# Ionic_Skin_Sensorized_Glove.net
KiCad netlist of a schematic drawn in EAGLE
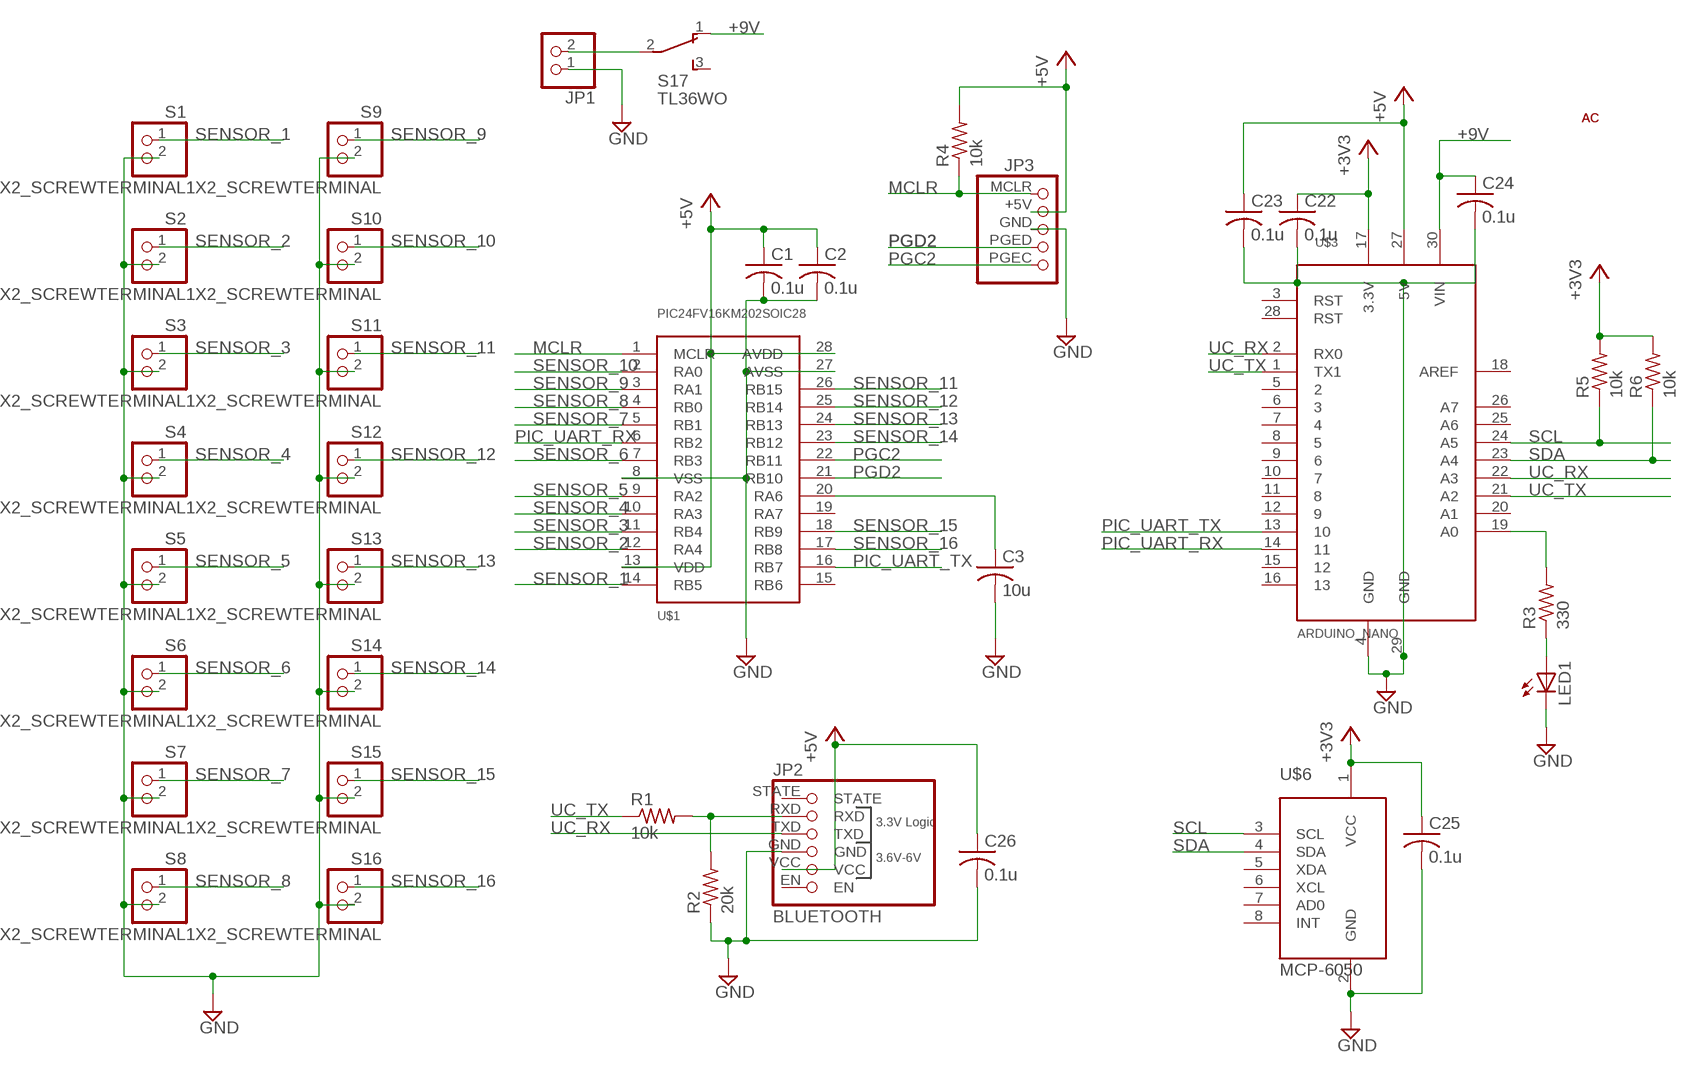
[diagram p0: schematic, sheet 1]

(export (version "E")
  (design (tool "Eeschema 10.0.6"))
  (components
    (comp (ref "C1")
      (value "0.1u")
      (footprint "eagle-import:C0805")
      (libsource (lib "eagle-import") (part "C-USC0805"))
    )
    (comp (ref "C2")
      (value "0.1u")
      (footprint "eagle-import:C0805")
      (libsource (lib "eagle-import") (part "C-USC0805"))
    )
    (comp (ref "C3")
      (value "10u")
      (footprint "eagle-import:C0805")
      (libsource (lib "eagle-import") (part "C-USC0805"))
    )
    (comp (ref "C22")
      (value "0.1u")
      (footprint "eagle-import:C0805")
      (libsource (lib "eagle-import") (part "C-USC0805"))
    )
    (comp (ref "C23")
      (value "0.1u")
      (footprint "eagle-import:C0805")
      (libsource (lib "eagle-import") (part "C-USC0805"))
    )
    (comp (ref "C24")
      (value "0.1u")
      (footprint "eagle-import:C0805")
      (libsource (lib "eagle-import") (part "C-USC0805"))
    )
    (comp (ref "C25")
      (value "0.1u")
      (footprint "eagle-import:C0805")
      (libsource (lib "eagle-import") (part "C-USC0805"))
    )
    (comp (ref "C26")
      (value "0.1u")
      (footprint "eagle-import:C0805")
      (libsource (lib "eagle-import") (part "C-USC0805"))
    )
    (comp (ref "JP1")
      (value "PINHD-1X2")
      (footprint "eagle-import:1X02")
      (libsource (lib "eagle-import") (part "PINHD-1X2"))
    )
    (comp (ref "JP2")
      (value "BLUETOOTH")
      (footprint "eagle-import:HC-06")
      (libsource (lib "eagle-import") (part "HC-06"))
    )
    (comp (ref "JP3")
      (value "PICKIT/90")
      (footprint "eagle-import:PICKIT_90")
      (libsource (lib "eagle-import") (part "PICKIT/90"))
    )
    (comp (ref "LED1")
      (value "LEDCHIPLED_0805")
      (footprint "eagle-import:CHIPLED_0805")
      (libsource (lib "eagle-import") (part "LEDCHIPLED_0805"))
    )
    (comp (ref "R1")
      (value "10k")
      (footprint "eagle-import:R0805")
      (libsource (lib "eagle-import") (part "R-US_R0805"))
    )
    (comp (ref "R2")
      (value "20k")
      (footprint "eagle-import:R0805")
      (libsource (lib "eagle-import") (part "R-US_R0805"))
    )
    (comp (ref "R3")
      (value "330")
      (footprint "eagle-import:R0805")
      (libsource (lib "eagle-import") (part "R-US_R0805"))
    )
    (comp (ref "R4")
      (value "10k")
      (footprint "eagle-import:R0805")
      (libsource (lib "eagle-import") (part "R-US_R0805"))
    )
    (comp (ref "R5")
      (value "10k")
      (footprint "eagle-import:R0805")
      (libsource (lib "eagle-import") (part "R-US_R0805"))
    )
    (comp (ref "R6")
      (value "10k")
      (footprint "eagle-import:R0805")
      (libsource (lib "eagle-import") (part "R-US_R0805"))
    )
    (comp (ref "S1")
      (value "1X2_SCREWTERMINAL")
      (footprint "eagle-import:1X2-2.54MM")
      (libsource (lib "eagle-import") (part "1X2_SCREWTERMINAL"))
    )
    (comp (ref "S2")
      (value "1X2_SCREWTERMINAL")
      (footprint "eagle-import:1X2-2.54MM")
      (libsource (lib "eagle-import") (part "1X2_SCREWTERMINAL"))
    )
    (comp (ref "S3")
      (value "1X2_SCREWTERMINAL")
      (footprint "eagle-import:1X2-2.54MM")
      (libsource (lib "eagle-import") (part "1X2_SCREWTERMINAL"))
    )
    (comp (ref "S4")
      (value "1X2_SCREWTERMINAL")
      (footprint "eagle-import:1X2-2.54MM")
      (libsource (lib "eagle-import") (part "1X2_SCREWTERMINAL"))
    )
    (comp (ref "S5")
      (value "1X2_SCREWTERMINAL")
      (footprint "eagle-import:1X2-2.54MM")
      (libsource (lib "eagle-import") (part "1X2_SCREWTERMINAL"))
    )
    (comp (ref "S6")
      (value "1X2_SCREWTERMINAL")
      (footprint "eagle-import:1X2-2.54MM")
      (libsource (lib "eagle-import") (part "1X2_SCREWTERMINAL"))
    )
    (comp (ref "S7")
      (value "1X2_SCREWTERMINAL")
      (footprint "eagle-import:1X2-2.54MM")
      (libsource (lib "eagle-import") (part "1X2_SCREWTERMINAL"))
    )
    (comp (ref "S8")
      (value "1X2_SCREWTERMINAL")
      (footprint "eagle-import:1X2-2.54MM")
      (libsource (lib "eagle-import") (part "1X2_SCREWTERMINAL"))
    )
    (comp (ref "S9")
      (value "1X2_SCREWTERMINAL")
      (footprint "eagle-import:1X2-2.54MM")
      (libsource (lib "eagle-import") (part "1X2_SCREWTERMINAL"))
    )
    (comp (ref "S10")
      (value "1X2_SCREWTERMINAL")
      (footprint "eagle-import:1X2-2.54MM")
      (libsource (lib "eagle-import") (part "1X2_SCREWTERMINAL"))
    )
    (comp (ref "S11")
      (value "1X2_SCREWTERMINAL")
      (footprint "eagle-import:1X2-2.54MM")
      (libsource (lib "eagle-import") (part "1X2_SCREWTERMINAL"))
    )
    (comp (ref "S12")
      (value "1X2_SCREWTERMINAL")
      (footprint "eagle-import:1X2-2.54MM")
      (libsource (lib "eagle-import") (part "1X2_SCREWTERMINAL"))
    )
    (comp (ref "S13")
      (value "1X2_SCREWTERMINAL")
      (footprint "eagle-import:1X2-2.54MM")
      (libsource (lib "eagle-import") (part "1X2_SCREWTERMINAL"))
    )
    (comp (ref "S14")
      (value "1X2_SCREWTERMINAL")
      (footprint "eagle-import:1X2-2.54MM")
      (libsource (lib "eagle-import") (part "1X2_SCREWTERMINAL"))
    )
    (comp (ref "S15")
      (value "1X2_SCREWTERMINAL")
      (footprint "eagle-import:1X2-2.54MM")
      (libsource (lib "eagle-import") (part "1X2_SCREWTERMINAL"))
    )
    (comp (ref "S16")
      (value "1X2_SCREWTERMINAL")
      (footprint "eagle-import:1X2-2.54MM")
      (libsource (lib "eagle-import") (part "1X2_SCREWTERMINAL"))
    )
    (comp (ref "S17")
      (value "TL36WO")
      (footprint "eagle-import:TL3XWO")
      (libsource (lib "eagle-import") (part "TL36WO"))
    )
    (comp (ref "U$1")
      (value "PIC24FV16KM202SOIC28")
      (footprint "eagle-import:SOIC28")
      (libsource (lib "eagle-import") (part "PIC24FV16KM202SOIC28"))
    )
    (comp (ref "U$3")
      (value "ARDUINO_NANO")
      (footprint "eagle-import:ARDUINO_NANO")
      (libsource (lib "eagle-import") (part "ARDUINO_NANO"))
    )
    (comp (ref "U$6")
      (value "MCP-6050")
      (footprint "eagle-import:MCP-6050_BREAKOUT")
      (libsource (lib "eagle-import") (part "MCP-6050"))
    )
    (comp (ref "U$7")
      (value "AC_TOP")
      (footprint "eagle-import:AC_TOP")
      (libsource (lib "eagle-import") (part "AC_TOP"))
    )
    (comp (ref "U$8")
      (value "AC_BOTTOM")
      (footprint "eagle-import:AC_BOTTOM")
      (libsource (lib "eagle-import") (part "AC_BOTTOM"))
    )
  )
  (nets
    (net (code "1") (name "+3V3") (class "Default")
      (node (ref "C22") (pin "1") (pinfunction "1_1") (pintype "passive"))
      (node (ref "C25") (pin "1") (pinfunction "1_1") (pintype "passive"))
      (node (ref "R5") (pin "2") (pinfunction "2_2") (pintype "passive"))
      (node (ref "R6") (pin "2") (pinfunction "2_2") (pintype "passive"))
      (node (ref "U$3") (pin "17") (pinfunction "3.3V_17") (pintype "bidirectional"))
      (node (ref "U$6") (pin "1") (pinfunction "VCC_1") (pintype "bidirectional"))
    )
    (net (code "2") (name "+5V") (class "Default")
      (node (ref "C1") (pin "1") (pinfunction "1_1") (pintype "passive"))
      (node (ref "C2") (pin "1") (pinfunction "1_1") (pintype "passive"))
      (node (ref "C23") (pin "1") (pinfunction "1_1") (pintype "passive"))
      (node (ref "C26") (pin "1") (pinfunction "1_1") (pintype "passive"))
      (node (ref "JP2") (pin "VCC") (pinfunction "VCC_VCC") (pintype "bidirectional"))
      (node (ref "JP3") (pin "+5V") (pinfunction "2_+5V") (pintype "passive"))
      (node (ref "R4") (pin "2") (pinfunction "2_2") (pintype "passive"))
      (node (ref "U$1") (pin "13") (pinfunction "VDD_13") (pintype "bidirectional"))
      (node (ref "U$1") (pin "28") (pinfunction "AVDD_28") (pintype "bidirectional"))
      (node (ref "U$3") (pin "27") (pinfunction "5V_27") (pintype "bidirectional"))
    )
    (net (code "3") (name "/+9V") (class "Default")
      (node (ref "C24") (pin "1") (pinfunction "1_1") (pintype "passive"))
      (node (ref "S17") (pin "1") (pinfunction "O_1") (pintype "passive"))
      (node (ref "U$3") (pin "30") (pinfunction "VIN_30") (pintype "bidirectional"))
    )
    (net (code "4") (name "/MCLR") (class "Default")
      (node (ref "JP3") (pin "MCLR") (pinfunction "1_MCLR") (pintype "passive"))
      (node (ref "R4") (pin "1") (pinfunction "1_1") (pintype "passive"))
      (node (ref "U$1") (pin "1") (pinfunction "MCLR_1") (pintype "bidirectional"))
    )
    (net (code "5") (name "/PGC2") (class "Default")
      (node (ref "JP3") (pin "PGEC") (pinfunction "5_PGEC") (pintype "passive"))
      (node (ref "U$1") (pin "22") (pinfunction "RB11_22") (pintype "bidirectional"))
    )
    (net (code "6") (name "/PGD2") (class "Default")
      (node (ref "JP3") (pin "PGED") (pinfunction "4_PGED") (pintype "passive"))
      (node (ref "U$1") (pin "21") (pinfunction "RB10_21") (pintype "bidirectional"))
    )
    (net (code "7") (name "/PIC_UART_RX") (class "Default")
      (node (ref "U$1") (pin "6") (pinfunction "RB2_6") (pintype "bidirectional"))
      (node (ref "U$3") (pin "14") (pinfunction "11_14") (pintype "bidirectional"))
    )
    (net (code "8") (name "/PIC_UART_TX") (class "Default")
      (node (ref "U$1") (pin "16") (pinfunction "RB7_16") (pintype "bidirectional"))
      (node (ref "U$3") (pin "13") (pinfunction "10_13") (pintype "bidirectional"))
    )
    (net (code "9") (name "/SCL") (class "Default")
      (node (ref "R5") (pin "1") (pinfunction "1_1") (pintype "passive"))
      (node (ref "U$3") (pin "24") (pinfunction "A5_24") (pintype "bidirectional"))
      (node (ref "U$6") (pin "3") (pinfunction "SCL_3") (pintype "bidirectional"))
    )
    (net (code "10") (name "/SDA") (class "Default")
      (node (ref "R6") (pin "1") (pinfunction "1_1") (pintype "passive"))
      (node (ref "U$3") (pin "23") (pinfunction "A4_23") (pintype "bidirectional"))
      (node (ref "U$6") (pin "4") (pinfunction "SDA_4") (pintype "bidirectional"))
    )
    (net (code "11") (name "/SENSOR_1") (class "Default")
      (node (ref "S1") (pin "1") (pinfunction "1_1") (pintype "passive"))
      (node (ref "U$1") (pin "14") (pinfunction "RB5_14") (pintype "bidirectional"))
    )
    (net (code "12") (name "/SENSOR_2") (class "Default")
      (node (ref "S2") (pin "1") (pinfunction "1_1") (pintype "passive"))
      (node (ref "U$1") (pin "12") (pinfunction "RA4_12") (pintype "bidirectional"))
    )
    (net (code "13") (name "/SENSOR_3") (class "Default")
      (node (ref "S3") (pin "1") (pinfunction "1_1") (pintype "passive"))
      (node (ref "U$1") (pin "11") (pinfunction "RB4_11") (pintype "bidirectional"))
    )
    (net (code "14") (name "/SENSOR_4") (class "Default")
      (node (ref "S4") (pin "1") (pinfunction "1_1") (pintype "passive"))
      (node (ref "U$1") (pin "10") (pinfunction "RA3_10") (pintype "bidirectional"))
    )
    (net (code "15") (name "/SENSOR_5") (class "Default")
      (node (ref "S5") (pin "1") (pinfunction "1_1") (pintype "passive"))
      (node (ref "U$1") (pin "9") (pinfunction "RA2_9") (pintype "bidirectional"))
    )
    (net (code "16") (name "/SENSOR_6") (class "Default")
      (node (ref "S6") (pin "1") (pinfunction "1_1") (pintype "passive"))
      (node (ref "U$1") (pin "7") (pinfunction "RB3_7") (pintype "bidirectional"))
    )
    (net (code "17") (name "/SENSOR_7") (class "Default")
      (node (ref "S7") (pin "1") (pinfunction "1_1") (pintype "passive"))
      (node (ref "U$1") (pin "5") (pinfunction "RB1_5") (pintype "bidirectional"))
    )
    (net (code "18") (name "/SENSOR_8") (class "Default")
      (node (ref "S8") (pin "1") (pinfunction "1_1") (pintype "passive"))
      (node (ref "U$1") (pin "4") (pinfunction "RB0_4") (pintype "bidirectional"))
    )
    (net (code "19") (name "/SENSOR_9") (class "Default")
      (node (ref "S9") (pin "1") (pinfunction "1_1") (pintype "passive"))
      (node (ref "U$1") (pin "3") (pinfunction "RA1_3") (pintype "bidirectional"))
    )
    (net (code "20") (name "/SENSOR_10") (class "Default")
      (node (ref "S10") (pin "1") (pinfunction "1_1") (pintype "passive"))
      (node (ref "U$1") (pin "2") (pinfunction "RA0_2") (pintype "bidirectional"))
    )
    (net (code "21") (name "/SENSOR_11") (class "Default")
      (node (ref "S11") (pin "1") (pinfunction "1_1") (pintype "passive"))
      (node (ref "U$1") (pin "26") (pinfunction "RB15_26") (pintype "bidirectional"))
    )
    (net (code "22") (name "/SENSOR_12") (class "Default")
      (node (ref "S12") (pin "1") (pinfunction "1_1") (pintype "passive"))
      (node (ref "U$1") (pin "25") (pinfunction "RB14_25") (pintype "bidirectional"))
    )
    (net (code "23") (name "/SENSOR_13") (class "Default")
      (node (ref "S13") (pin "1") (pinfunction "1_1") (pintype "passive"))
      (node (ref "U$1") (pin "24") (pinfunction "RB13_24") (pintype "bidirectional"))
    )
    (net (code "24") (name "/SENSOR_14") (class "Default")
      (node (ref "S14") (pin "1") (pinfunction "1_1") (pintype "passive"))
      (node (ref "U$1") (pin "23") (pinfunction "RB12_23") (pintype "bidirectional"))
    )
    (net (code "25") (name "/SENSOR_15") (class "Default")
      (node (ref "S15") (pin "1") (pinfunction "1_1") (pintype "passive"))
      (node (ref "U$1") (pin "18") (pinfunction "RB9_18") (pintype "bidirectional"))
    )
    (net (code "26") (name "/SENSOR_16") (class "Default")
      (node (ref "S16") (pin "1") (pinfunction "1_1") (pintype "passive"))
      (node (ref "U$1") (pin "17") (pinfunction "RB8_17") (pintype "bidirectional"))
    )
    (net (code "27") (name "/UC_RX") (class "Default")
      (node (ref "JP2") (pin "TXD") (pinfunction "TXD_TXD") (pintype "bidirectional"))
      (node (ref "U$3") (pin "2") (pinfunction "RX0_2") (pintype "bidirectional"))
      (node (ref "U$3") (pin "22") (pinfunction "A3_22") (pintype "bidirectional"))
    )
    (net (code "28") (name "/UC_TX") (class "Default")
      (node (ref "R1") (pin "1") (pinfunction "1_1") (pintype "passive"))
      (node (ref "U$3") (pin "1") (pinfunction "TX1_1") (pintype "bidirectional"))
      (node (ref "U$3") (pin "21") (pinfunction "A2_21") (pintype "bidirectional"))
    )
    (net (code "29") (name "GND") (class "Default")
      (node (ref "C1") (pin "2") (pinfunction "2_2") (pintype "passive"))
      (node (ref "C2") (pin "2") (pinfunction "2_2") (pintype "passive"))
      (node (ref "C22") (pin "2") (pinfunction "2_2") (pintype "passive"))
      (node (ref "C23") (pin "2") (pinfunction "2_2") (pintype "passive"))
      (node (ref "C24") (pin "2") (pinfunction "2_2") (pintype "passive"))
      (node (ref "C25") (pin "2") (pinfunction "2_2") (pintype "passive"))
      (node (ref "C26") (pin "2") (pinfunction "2_2") (pintype "passive"))
      (node (ref "C3") (pin "2") (pinfunction "2_2") (pintype "passive"))
      (node (ref "JP1") (pin "1") (pinfunction "1_1") (pintype "passive"))
      (node (ref "JP2") (pin "GND") (pinfunction "GND_GND") (pintype "bidirectional"))
      (node (ref "JP3") (pin "GND") (pinfunction "3_GND") (pintype "passive"))
      (node (ref "LED1") (pin "C") (pinfunction "C_C") (pintype "passive"))
      (node (ref "R2") (pin "1") (pinfunction "1_1") (pintype "passive"))
      (node (ref "S1") (pin "2") (pinfunction "2_2") (pintype "passive"))
      (node (ref "S10") (pin "2") (pinfunction "2_2") (pintype "passive"))
      (node (ref "S11") (pin "2") (pinfunction "2_2") (pintype "passive"))
      (node (ref "S12") (pin "2") (pinfunction "2_2") (pintype "passive"))
      (node (ref "S13") (pin "2") (pinfunction "2_2") (pintype "passive"))
      (node (ref "S14") (pin "2") (pinfunction "2_2") (pintype "passive"))
      (node (ref "S15") (pin "2") (pinfunction "2_2") (pintype "passive"))
      (node (ref "S16") (pin "2") (pinfunction "2_2") (pintype "passive"))
      (node (ref "S2") (pin "2") (pinfunction "2_2") (pintype "passive"))
      (node (ref "S3") (pin "2") (pinfunction "2_2") (pintype "passive"))
      (node (ref "S4") (pin "2") (pinfunction "2_2") (pintype "passive"))
      (node (ref "S5") (pin "2") (pinfunction "2_2") (pintype "passive"))
      (node (ref "S6") (pin "2") (pinfunction "2_2") (pintype "passive"))
      (node (ref "S7") (pin "2") (pinfunction "2_2") (pintype "passive"))
      (node (ref "S8") (pin "2") (pinfunction "2_2") (pintype "passive"))
      (node (ref "S9") (pin "2") (pinfunction "2_2") (pintype "passive"))
      (node (ref "U$1") (pin "27") (pinfunction "AVSS_27") (pintype "bidirectional"))
      (node (ref "U$1") (pin "8") (pinfunction "VSS_8") (pintype "bidirectional"))
      (node (ref "U$3") (pin "29") (pinfunction "GND_29") (pintype "bidirectional"))
      (node (ref "U$3") (pin "4") (pinfunction "GND_4") (pintype "bidirectional"))
      (node (ref "U$6") (pin "2") (pinfunction "GND_2") (pintype "bidirectional"))
    )
    (net (code "30") (name "Net-(JP2-PadRXD)") (class "Default")
      (node (ref "JP2") (pin "RXD") (pinfunction "RXD_RXD") (pintype "bidirectional"))
      (node (ref "R1") (pin "2") (pinfunction "2_2") (pintype "passive"))
      (node (ref "R2") (pin "2") (pinfunction "2_2") (pintype "passive"))
    )
    (net (code "31") (name "Net-(LED1-PadA)") (class "Default")
      (node (ref "LED1") (pin "A") (pinfunction "A_A") (pintype "passive"))
      (node (ref "R3") (pin "1") (pinfunction "1_1") (pintype "passive"))
    )
    (net (code "32") (name "Net-(S17-P)") (class "Default")
      (node (ref "JP1") (pin "2") (pinfunction "2_2") (pintype "passive"))
      (node (ref "S17") (pin "2") (pinfunction "P_2") (pintype "passive"))
    )
    (net (code "33") (name "Net-(U$1-RA6)") (class "Default")
      (node (ref "C3") (pin "1") (pinfunction "1_1") (pintype "passive"))
      (node (ref "U$1") (pin "20") (pinfunction "RA6_20") (pintype "bidirectional"))
    )
    (net (code "34") (name "Net-(U$3-A0)") (class "Default")
      (node (ref "R3") (pin "2") (pinfunction "2_2") (pintype "passive"))
      (node (ref "U$3") (pin "19") (pinfunction "A0_19") (pintype "bidirectional"))
    )
    (net (code "35") (name "unconnected-(JP2-PadEN)") (class "Default")
      (node (ref "JP2") (pin "EN") (pinfunction "EN_EN") (pintype "bidirectional"))
    )
    (net (code "36") (name "unconnected-(JP2-PadSTATE)") (class "Default")
      (node (ref "JP2") (pin "STATE") (pinfunction "STATE_STATE") (pintype "bidirectional"))
    )
    (net (code "37") (name "unconnected-(S17-S-Pad3)") (class "Default")
      (node (ref "S17") (pin "3") (pinfunction "S_3") (pintype "passive"))
    )
    (net (code "38") (name "unconnected-(U$1-RA7-Pad19)") (class "Default")
      (node (ref "U$1") (pin "19") (pinfunction "RA7_19") (pintype "bidirectional"))
    )
    (net (code "39") (name "unconnected-(U$1-RB6-Pad15)") (class "Default")
      (node (ref "U$1") (pin "15") (pinfunction "RB6_15") (pintype "bidirectional"))
    )
    (net (code "40") (name "unconnected-(U$3-2-Pad5)") (class "Default")
      (node (ref "U$3") (pin "5") (pinfunction "2_5") (pintype "bidirectional"))
    )
    (net (code "41") (name "unconnected-(U$3-3-Pad6)") (class "Default")
      (node (ref "U$3") (pin "6") (pinfunction "3_6") (pintype "bidirectional"))
    )
    (net (code "42") (name "unconnected-(U$3-4-Pad7)") (class "Default")
      (node (ref "U$3") (pin "7") (pinfunction "4_7") (pintype "bidirectional"))
    )
    (net (code "43") (name "unconnected-(U$3-5-Pad8)") (class "Default")
      (node (ref "U$3") (pin "8") (pinfunction "5_8") (pintype "bidirectional"))
    )
    (net (code "44") (name "unconnected-(U$3-6-Pad9)") (class "Default")
      (node (ref "U$3") (pin "9") (pinfunction "6_9") (pintype "bidirectional"))
    )
    (net (code "45") (name "unconnected-(U$3-7-Pad10)") (class "Default")
      (node (ref "U$3") (pin "10") (pinfunction "7_10") (pintype "bidirectional"))
    )
    (net (code "46") (name "unconnected-(U$3-8-Pad11)") (class "Default")
      (node (ref "U$3") (pin "11") (pinfunction "8_11") (pintype "bidirectional"))
    )
    (net (code "47") (name "unconnected-(U$3-9-Pad12)") (class "Default")
      (node (ref "U$3") (pin "12") (pinfunction "9_12") (pintype "bidirectional"))
    )
    (net (code "48") (name "unconnected-(U$3-12-Pad15)") (class "Default")
      (node (ref "U$3") (pin "15") (pinfunction "12_15") (pintype "bidirectional"))
    )
    (net (code "49") (name "unconnected-(U$3-13-Pad16)") (class "Default")
      (node (ref "U$3") (pin "16") (pinfunction "13_16") (pintype "bidirectional"))
    )
    (net (code "50") (name "unconnected-(U$3-A1-Pad20)") (class "Default")
      (node (ref "U$3") (pin "20") (pinfunction "A1_20") (pintype "bidirectional"))
    )
    (net (code "51") (name "unconnected-(U$3-A6-Pad25)") (class "Default")
      (node (ref "U$3") (pin "25") (pinfunction "A6_25") (pintype "bidirectional"))
    )
    (net (code "52") (name "unconnected-(U$3-A7-Pad26)") (class "Default")
      (node (ref "U$3") (pin "26") (pinfunction "A7_26") (pintype "bidirectional"))
    )
    (net (code "53") (name "unconnected-(U$3-AREF-Pad18)") (class "Default")
      (node (ref "U$3") (pin "18") (pinfunction "AREF_18") (pintype "bidirectional"))
    )
    (net (code "54") (name "unconnected-(U$3-RST-Pad3)") (class "Default")
      (node (ref "U$3") (pin "3") (pinfunction "RST_3") (pintype "bidirectional"))
    )
    (net (code "55") (name "unconnected-(U$3-RST-Pad28)") (class "Default")
      (node (ref "U$3") (pin "28") (pinfunction "RST_28") (pintype "bidirectional"))
    )
    (net (code "56") (name "unconnected-(U$6-AD0-Pad7)") (class "Default")
      (node (ref "U$6") (pin "7") (pinfunction "AD0_7") (pintype "bidirectional"))
    )
    (net (code "57") (name "unconnected-(U$6-INT-Pad8)") (class "Default")
      (node (ref "U$6") (pin "8") (pinfunction "INT_8") (pintype "bidirectional"))
    )
    (net (code "58") (name "unconnected-(U$6-XCL-Pad6)") (class "Default")
      (node (ref "U$6") (pin "6") (pinfunction "XCL_6") (pintype "bidirectional"))
    )
    (net (code "59") (name "unconnected-(U$6-XDA-Pad5)") (class "Default")
      (node (ref "U$6") (pin "5") (pinfunction "XDA_5") (pintype "bidirectional"))
    )
  )
)
